# NoiseSource.net
KiCad netlist of a schematic drawn in Altium Designer
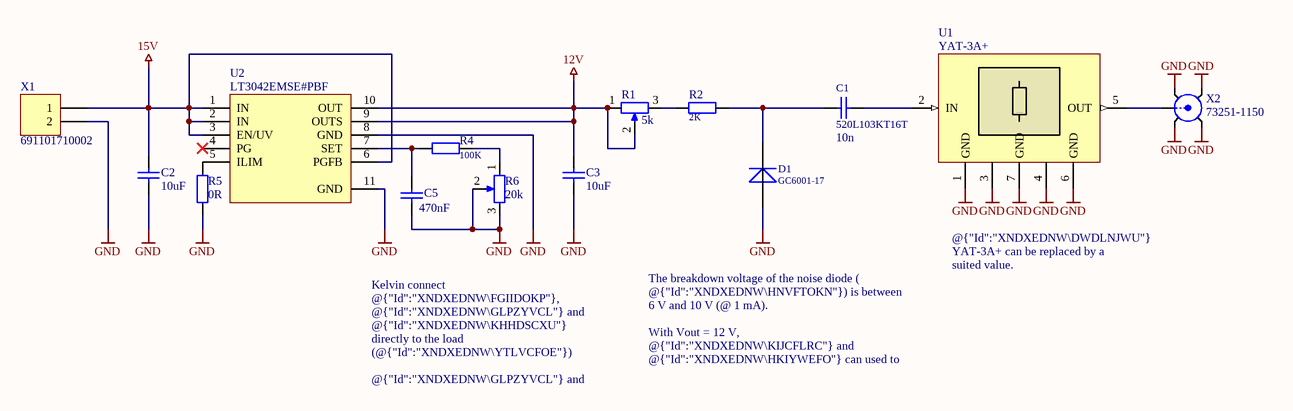
[diagram p0: NoiseSource.SchDoc]

(export (version "E")
  (design (tool "Eeschema 10.0.6"))
  (components
    (comp (ref "C1")
      (value "520L103KT16T")
      (footprint "CAP-0402[1005] - RFL")
      (description "10n, X7R, 10%, 16V, 16kHz - 16GHz, 0402")
      (fields (field (name "SHORTDESCRIPTION") "10n") (field (name "MANUFACTURER") "ATC"))
      (libsource (lib "OST Vault") (part "Capacitor"))
    )
    (comp (ref "C2")
      (value "GRM188R61E106KA73D")
      (footprint "Generic_Cap0603_2_RW")
      (description "10uF, X5R, 10%, 25V")
      (fields (field (name "MANUFACTURER") "Murata") (field (name "SHORTDESCRIPTION") "10uF"))
      (libsource (lib "OST Vault") (part "Generic_Capacitor_2"))
    )
    (comp (ref "C3")
      (value "GRM188R61E106KA73D")
      (footprint "Generic_Cap0603_2_RW")
      (description "10uF, X5R, 10%, 25V")
      (fields (field (name "MANUFACTURER") "Murata") (field (name "SHORTDESCRIPTION") "10uF"))
      (libsource (lib "OST Vault") (part "Generic_Capacitor_2"))
    )
    (comp (ref "C5")
      (value "UMK107B7474KA-TR")
      (footprint "Generic_Cap0603_2_RW")
      (description "470nF, X7R, 10%, 50V")
      (fields (field (name "SHORTDESCRIPTION") "470nF") (field (name "MANUFACTURER") "Taiyo Yuden"))
      (libsource (lib "OST Vault") (part "Generic_Capacitor_2"))
    )
    (comp (ref "D1")
      (value "GC6001-17")
      (footprint "Microsemi_GC6001-17_2")
      (description "Microwave Noise Diode, 0.1 - 18 GHz")
      (fields (field (name "MANUFACTURER") "Microchip"))
      (libsource (lib "OST Vault") (part "Diode"))
    )
    (comp (ref "R1")
      (value "3312J-1-502E")
      (footprint "BOURNS_3312_3")
      (description "SMD Trimmer, 5k, 2mm")
      (fields (field (name "SHORTDESCRIPTION") "5k") (field (name "MANUFACTURER") "Bourns"))
      (libsource (lib "OST Vault") (part "Variable Resistor"))
    )
    (comp (ref "R2")
      (value "2K")
      (footprint "RES-0603[1608] - RFL")
      (description "2K 0.1W 1% 0603 (1608 Metric)  SMD")
      (fields (field (name "Comment") "2K 1% 0603(1608)"))
      (libsource (lib "") (part "R_1"))
    )
    (comp (ref "R4")
      (value "100K")
      (footprint "RES-0603[1608] - RFL")
      (description "100K 0.1W 1% 0603 (1608 Metric)  SMD")
      (fields (field (name "Comment") "100K 1% 0603(1608)"))
      (libsource (lib "OST Vault") (part "R"))
    )
    (comp (ref "R5")
      (value "0R")
      (footprint "Generic_Res0603_2_RW")
      (description "0R, 1%, 0603")
      (fields (field (name "MANUFACTURER") "Generic"))
      (libsource (lib "OST Vault") (part "Generic_Resistor_2"))
    )
    (comp (ref "R6")
      (value "3312J-1-203E")
      (footprint "BOURNS_3312_3")
      (description "SMD Trimmer, 20k, 2mm")
      (fields (field (name "MANUFACTURER") "Bourns") (field (name "SHORTDESCRIPTION") "20k"))
      (libsource (lib "") (part "Variable Resistor_1"))
    )
    (comp (ref "U1")
      (value "YAT-3A+")
      (footprint "MiniCircuit_MC1630_R")
      (description "Fixed Attenuator, DC - 18 GHz, 50R, 3dB, 2W")
      (fields (field (name "MANUFACTURER") "MiniCircuits"))
      (libsource (lib "OST Vault") (part "MINICIRCUITS_YAT-XX_7"))
    )
    (comp (ref "U2")
      (value "LT3042EMSE#PBF")
      (footprint "ANALOG_MSOP10_11")
      (description "20V, 200mA, Ultralow Noise, Ultrahigh PSRR RF Linear Regulator, ADJ")
      (fields (field (name "MANUFACTURER") "Analog"))
      (libsource (lib "OST Vault") (part "ANALOG_LT3042_DFN10_11"))
    )
    (comp (ref "X1")
      (value "691101710002")
      (footprint "WURTH_691101710002_2_RWH")
      (description "Screw Terminal, 2 Pos, 5 mm")
      (fields (field (name "MANUFACTURER") "Wurth"))
      (libsource (lib "OST Vault") (part "Connector 2 Pos"))
    )
    (comp (ref "X2")
      (value "73251-1150")
      (footprint "Amphenol_SMA-EDGE-MOUNT_3_H")
      (description "SMA, Female, 1.5mm Edge Mount")
      (fields (field (name "MANUFACTURER") "Molex"))
      (libsource (lib "OST Vault") (part "Coax Connector 5 Pin"))
    )
  )
  (nets
    (net (code "1") (name "12V") (class "Default")
      (node (ref "C3") (pin "2") (pinfunction "2_2") (pintype "passive"))
      (node (ref "R1") (pin "1") (pinfunction "TOP_1") (pintype "passive"))
      (node (ref "R1") (pin "2") (pinfunction "TAP_2") (pintype "passive"))
      (node (ref "U2") (pin "10") (pinfunction "OUT_10") (pintype "passive"))
      (node (ref "U2") (pin "9") (pinfunction "OUTS_9") (pintype "passive"))
    )
    (net (code "2") (name "15V") (class "Default")
      (node (ref "C2") (pin "2") (pinfunction "2_2") (pintype "passive"))
      (node (ref "U2") (pin "1") (pinfunction "IN_1") (pintype "passive"))
      (node (ref "U2") (pin "2") (pinfunction "IN_2") (pintype "passive"))
      (node (ref "U2") (pin "3") (pinfunction "EN/UV_3") (pintype "passive"))
      (node (ref "U2") (pin "6") (pinfunction "PGFB_6") (pintype "passive"))
      (node (ref "X1") (pin "1") (pinfunction "1_1") (pintype "passive"))
    )
    (net (code "3") (name "GND") (class "Default")
      (node (ref "C2") (pin "1") (pinfunction "1_1") (pintype "passive"))
      (node (ref "C3") (pin "1") (pinfunction "1_1") (pintype "passive"))
      (node (ref "C5") (pin "2") (pinfunction "2_2") (pintype "passive"))
      (node (ref "D1") (pin "2") (pinfunction "A_2") (pintype "passive"))
      (node (ref "R5") (pin "2") (pinfunction "2_2") (pintype "passive"))
      (node (ref "R6") (pin "2") (pinfunction "TAP_2") (pintype "passive"))
      (node (ref "R6") (pin "3") (pinfunction "BOT_3") (pintype "passive"))
      (node (ref "U1") (pin "1") (pinfunction "GND_1") (pintype "power_in"))
      (node (ref "U1") (pin "3") (pinfunction "GND_3") (pintype "power_in"))
      (node (ref "U1") (pin "4") (pinfunction "GND_4") (pintype "passive"))
      (node (ref "U1") (pin "6") (pinfunction "GND_6") (pintype "power_in"))
      (node (ref "U1") (pin "7") (pinfunction "GND_7") (pintype "power_in"))
      (node (ref "U2") (pin "11") (pinfunction "GND_11") (pintype "passive"))
      (node (ref "U2") (pin "8") (pinfunction "GND_8") (pintype "passive"))
      (node (ref "X1") (pin "2") (pinfunction "2_2") (pintype "passive"))
      (node (ref "X2") (pin "2") (pinfunction "2_2") (pintype "passive"))
      (node (ref "X2") (pin "3") (pinfunction "3_3") (pintype "passive"))
      (node (ref "X2") (pin "4") (pinfunction "4_4") (pintype "passive"))
      (node (ref "X2") (pin "5") (pinfunction "5_5") (pintype "passive"))
    )
    (net (code "4") (name "Net-(D1-K)") (class "Default")
      (node (ref "C1") (pin "2") (pinfunction "2_2") (pintype "passive"))
      (node (ref "D1") (pin "1") (pinfunction "K_1") (pintype "passive"))
      (node (ref "R2") (pin "1") (pinfunction "1_1") (pintype "passive"))
    )
    (net (code "5") (name "Net-(R1-BOT)") (class "Default")
      (node (ref "R1") (pin "3") (pinfunction "BOT_3") (pintype "passive"))
      (node (ref "R2") (pin "2") (pinfunction "2_2") (pintype "passive"))
    )
    (net (code "6") (name "Net-(R6-TOP)") (class "Default")
      (node (ref "R4") (pin "2") (pinfunction "2_2") (pintype "passive"))
      (node (ref "R6") (pin "1") (pinfunction "TOP_1") (pintype "passive"))
    )
    (net (code "7") (name "Net-(U1-IN)") (class "Default")
      (node (ref "C1") (pin "1") (pinfunction "1_1") (pintype "passive"))
      (node (ref "U1") (pin "2") (pinfunction "IN_2") (pintype "input"))
    )
    (net (code "8") (name "Net-(U1-OUT)") (class "Default")
      (node (ref "U1") (pin "5") (pinfunction "OUT_5") (pintype "output"))
      (node (ref "X2") (pin "1") (pinfunction "1_1") (pintype "passive"))
    )
    (net (code "9") (name "Net-(U2-ILIM)") (class "Default")
      (node (ref "R5") (pin "1") (pinfunction "1_1") (pintype "passive"))
      (node (ref "U2") (pin "5") (pinfunction "ILIM_5") (pintype "passive"))
    )
    (net (code "10") (name "Net-(U2-SET)") (class "Default")
      (node (ref "C5") (pin "1") (pinfunction "1_1") (pintype "passive"))
      (node (ref "R4") (pin "1") (pinfunction "1_1") (pintype "passive"))
      (node (ref "U2") (pin "7") (pinfunction "SET_7") (pintype "passive"))
    )
    (net (code "11") (name "unconnected-(U2-PG-Pad4)") (class "Default")
      (node (ref "U2") (pin "4") (pinfunction "PG_4") (pintype "passive+no_connect"))
    )
  )
)
